# Program_Counter.net
KiCad netlist of a schematic drawn in Altium Designer
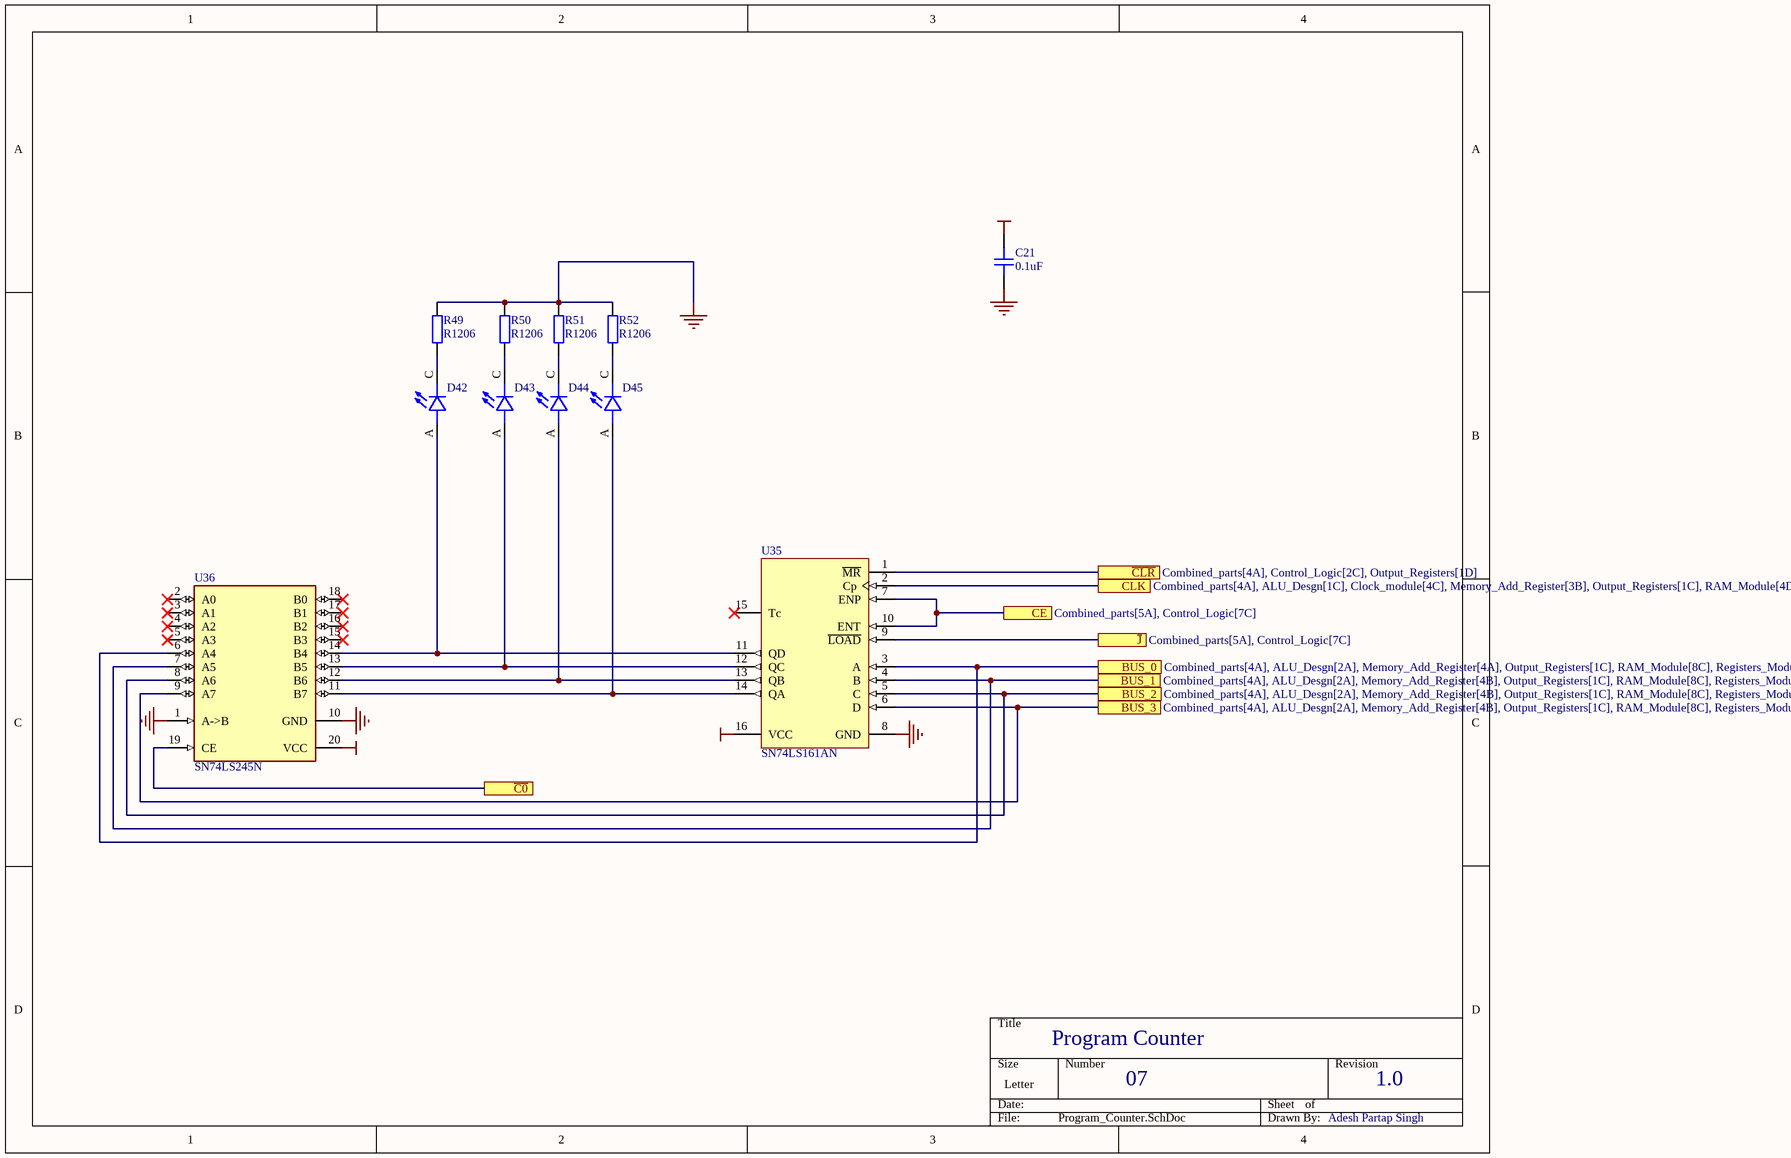
[diagram p0: Program_Counter.SchDoc]

(export (version "E")
  (design (tool "Eeschema 10.0.6"))
  (components
    (comp (ref "C21")
      (value "0.1uF")
      (footprint "CAP_0805")
      (description "Capacitor SMD 0805")
      (libsource (lib "Schematic-Lib-PhilsLab") (part "CAP_0805"))
    )
    (comp (ref "D42")
      (value "L08R5000Q1")
      (footprint "LEDRD254W57D500H1070")
      (fields (field (name "MF") "LED Technology"))
      (libsource (lib "8BIT_COMP_LIB") (part "L08R5000Q1"))
    )
    (comp (ref "D43")
      (value "L08R5000Q1")
      (footprint "LEDRD254W57D500H1070")
      (fields (field (name "MF") "LED Technology"))
      (libsource (lib "8BIT_COMP_LIB") (part "L08R5000Q1"))
    )
    (comp (ref "D44")
      (value "L08R5000Q1")
      (footprint "LEDRD254W57D500H1070")
      (fields (field (name "MF") "LED Technology"))
      (libsource (lib "8BIT_COMP_LIB") (part "L08R5000Q1"))
    )
    (comp (ref "D45")
      (value "L08R5000Q1")
      (footprint "LEDRD254W57D500H1070")
      (fields (field (name "MF") "LED Technology"))
      (libsource (lib "8BIT_COMP_LIB") (part "L08R5000Q1"))
    )
    (comp (ref "R49")
      (value "R1206")
      (footprint "RES_1206")
      (description "Resistor SMD 1206")
      (libsource (lib "Schematic-Lib-PhilsLab") (part "RES_1206"))
    )
    (comp (ref "R50")
      (value "R1206")
      (footprint "RES_1206")
      (description "Resistor SMD 1206")
      (libsource (lib "Schematic-Lib-PhilsLab") (part "RES_1206"))
    )
    (comp (ref "R51")
      (value "R1206")
      (footprint "RES_1206")
      (description "Resistor SMD 1206")
      (libsource (lib "Schematic-Lib-PhilsLab") (part "RES_1206"))
    )
    (comp (ref "R52")
      (value "R1206")
      (footprint "RES_1206")
      (description "Resistor SMD 1206")
      (libsource (lib "Schematic-Lib-PhilsLab") (part "RES_1206"))
    )
    (comp (ref "U35")
      (value "SN74LS161AN")
      (footprint "N0016A")
      (description "Synchronous 4-Bit Binary Counters, N0016A, TUBE")
      (fields
        (field (name "GENERIC PART NUMBER") "SN74LS161A")
        (field (name "MANUFACTURER") "Texas Instruments")
      )
      (libsource (lib "8BIT_COMP_LIB") (part "IC_BINARY_COUNTER-4-BIT_16DIP"))
    )
    (comp (ref "U36")
      (value "SN74LS245N")
      (footprint "FP-N0020A-MFG")
      (description "IC TXRX NON-INVERT 5.25V 20DIP")
      (libsource (lib "8BIT_COMP_LIB") (part "CMP-1620-00419-3"))
    )
  )
  (nets
    (net (code "1") (name "/BUS_0") (class "Default")
      (node (ref "U35") (pin "3") (pinfunction "A_3") (pintype "input"))
      (node (ref "U36") (pin "6") (pinfunction "A4_6") (pintype "bidirectional"))
    )
    (net (code "2") (name "/BUS_1") (class "Default")
      (node (ref "U35") (pin "4") (pinfunction "B_4") (pintype "input"))
      (node (ref "U36") (pin "7") (pinfunction "A5_7") (pintype "bidirectional"))
    )
    (net (code "3") (name "/BUS_2") (class "Default")
      (node (ref "U35") (pin "5") (pinfunction "C_5") (pintype "input"))
      (node (ref "U36") (pin "8") (pinfunction "A6_8") (pintype "bidirectional"))
    )
    (net (code "4") (name "/BUS_3") (class "Default")
      (node (ref "U35") (pin "6") (pinfunction "D_6") (pintype "input"))
      (node (ref "U36") (pin "9") (pinfunction "A7_9") (pintype "bidirectional"))
    )
    (net (code "5") (name "/CE") (class "Default")
      (node (ref "U35") (pin "10") (pinfunction "ENT_10") (pintype "input"))
      (node (ref "U35") (pin "7") (pinfunction "ENP_7") (pintype "input"))
    )
    (net (code "6") (name "/CLK") (class "Default")
      (node (ref "U35") (pin "2") (pinfunction "Cp_2") (pintype "input"))
    )
    (net (code "7") (name "/~{C0}") (class "Default")
      (node (ref "U36") (pin "19") (pinfunction "CE_19") (pintype "input"))
    )
    (net (code "8") (name "/~{CLR}") (class "Default")
      (node (ref "U35") (pin "1") (pinfunction "~{MR}_1") (pintype "power_in"))
    )
    (net (code "9") (name "/~{J}") (class "Default")
      (node (ref "U35") (pin "9") (pinfunction "~{LOAD}_9") (pintype "input"))
    )
    (net (code "10") (name "GND") (class "Default")
      (node (ref "C21") (pin "1") (pinfunction "1_1") (pintype "passive"))
      (node (ref "R49") (pin "2") (pinfunction "2_2") (pintype "passive"))
      (node (ref "R50") (pin "2") (pinfunction "2_2") (pintype "passive"))
      (node (ref "R51") (pin "2") (pinfunction "2_2") (pintype "passive"))
      (node (ref "R52") (pin "2") (pinfunction "2_2") (pintype "passive"))
      (node (ref "U35") (pin "8") (pinfunction "GND_8") (pintype "power_in"))
      (node (ref "U36") (pin "1") (pinfunction "A->B_1") (pintype "input"))
      (node (ref "U36") (pin "10") (pinfunction "GND_10") (pintype "power_in"))
    )
    (net (code "11") (name "Net-(D42-PadC)") (class "Default")
      (node (ref "D42") (pin "C") (pinfunction "C_C") (pintype "passive"))
      (node (ref "R49") (pin "1") (pinfunction "1_1") (pintype "passive"))
    )
    (net (code "12") (name "Net-(D43-PadC)") (class "Default")
      (node (ref "D43") (pin "C") (pinfunction "C_C") (pintype "passive"))
      (node (ref "R50") (pin "1") (pinfunction "1_1") (pintype "passive"))
    )
    (net (code "13") (name "Net-(D44-PadC)") (class "Default")
      (node (ref "D44") (pin "C") (pinfunction "C_C") (pintype "passive"))
      (node (ref "R51") (pin "1") (pinfunction "1_1") (pintype "passive"))
    )
    (net (code "14") (name "Net-(D45-PadC)") (class "Default")
      (node (ref "D45") (pin "C") (pinfunction "C_C") (pintype "passive"))
      (node (ref "R52") (pin "1") (pinfunction "1_1") (pintype "passive"))
    )
    (net (code "15") (name "Net-(U35-QA)") (class "Default")
      (node (ref "D45") (pin "A") (pinfunction "A_A") (pintype "passive"))
      (node (ref "U35") (pin "14") (pinfunction "QA_14") (pintype "output"))
      (node (ref "U36") (pin "11") (pinfunction "B7_11") (pintype "bidirectional"))
    )
    (net (code "16") (name "Net-(U35-QB)") (class "Default")
      (node (ref "D44") (pin "A") (pinfunction "A_A") (pintype "passive"))
      (node (ref "U35") (pin "13") (pinfunction "QB_13") (pintype "output"))
      (node (ref "U36") (pin "12") (pinfunction "B6_12") (pintype "bidirectional"))
    )
    (net (code "17") (name "Net-(U35-QC)") (class "Default")
      (node (ref "D43") (pin "A") (pinfunction "A_A") (pintype "passive"))
      (node (ref "U35") (pin "12") (pinfunction "QC_12") (pintype "output"))
      (node (ref "U36") (pin "13") (pinfunction "B5_13") (pintype "bidirectional"))
    )
    (net (code "18") (name "Net-(U35-QD)") (class "Default")
      (node (ref "D42") (pin "A") (pinfunction "A_A") (pintype "passive"))
      (node (ref "U35") (pin "11") (pinfunction "QD_11") (pintype "output"))
      (node (ref "U36") (pin "14") (pinfunction "B4_14") (pintype "bidirectional"))
    )
    (net (code "19") (name "VCC") (class "Default")
      (node (ref "C21") (pin "2") (pinfunction "2_2") (pintype "passive"))
      (node (ref "U35") (pin "16") (pinfunction "VCC_16") (pintype "power_in"))
      (node (ref "U36") (pin "20") (pinfunction "VCC_20") (pintype "power_in"))
    )
    (net (code "20") (name "unconnected-(U35-Tc-Pad15)") (class "Default")
      (node (ref "U35") (pin "15") (pinfunction "Tc_15") (pintype "power_in+no_connect"))
    )
    (net (code "21") (name "unconnected-(U36-A0-Pad2)") (class "Default")
      (node (ref "U36") (pin "2") (pinfunction "A0_2") (pintype "bidirectional+no_connect"))
    )
    (net (code "22") (name "unconnected-(U36-A1-Pad3)") (class "Default")
      (node (ref "U36") (pin "3") (pinfunction "A1_3") (pintype "bidirectional+no_connect"))
    )
    (net (code "23") (name "unconnected-(U36-A2-Pad4)") (class "Default")
      (node (ref "U36") (pin "4") (pinfunction "A2_4") (pintype "bidirectional+no_connect"))
    )
    (net (code "24") (name "unconnected-(U36-A3-Pad5)") (class "Default")
      (node (ref "U36") (pin "5") (pinfunction "A3_5") (pintype "bidirectional+no_connect"))
    )
    (net (code "25") (name "unconnected-(U36-B0-Pad18)") (class "Default")
      (node (ref "U36") (pin "18") (pinfunction "B0_18") (pintype "bidirectional+no_connect"))
    )
    (net (code "26") (name "unconnected-(U36-B1-Pad17)") (class "Default")
      (node (ref "U36") (pin "17") (pinfunction "B1_17") (pintype "bidirectional+no_connect"))
    )
    (net (code "27") (name "unconnected-(U36-B2-Pad16)") (class "Default")
      (node (ref "U36") (pin "16") (pinfunction "B2_16") (pintype "bidirectional+no_connect"))
    )
    (net (code "28") (name "unconnected-(U36-B3-Pad15)") (class "Default")
      (node (ref "U36") (pin "15") (pinfunction "B3_15") (pintype "bidirectional+no_connect"))
    )
  )
)
